# PIDDYBOT_V1.net
KiCad netlist of a schematic drawn in EAGLE
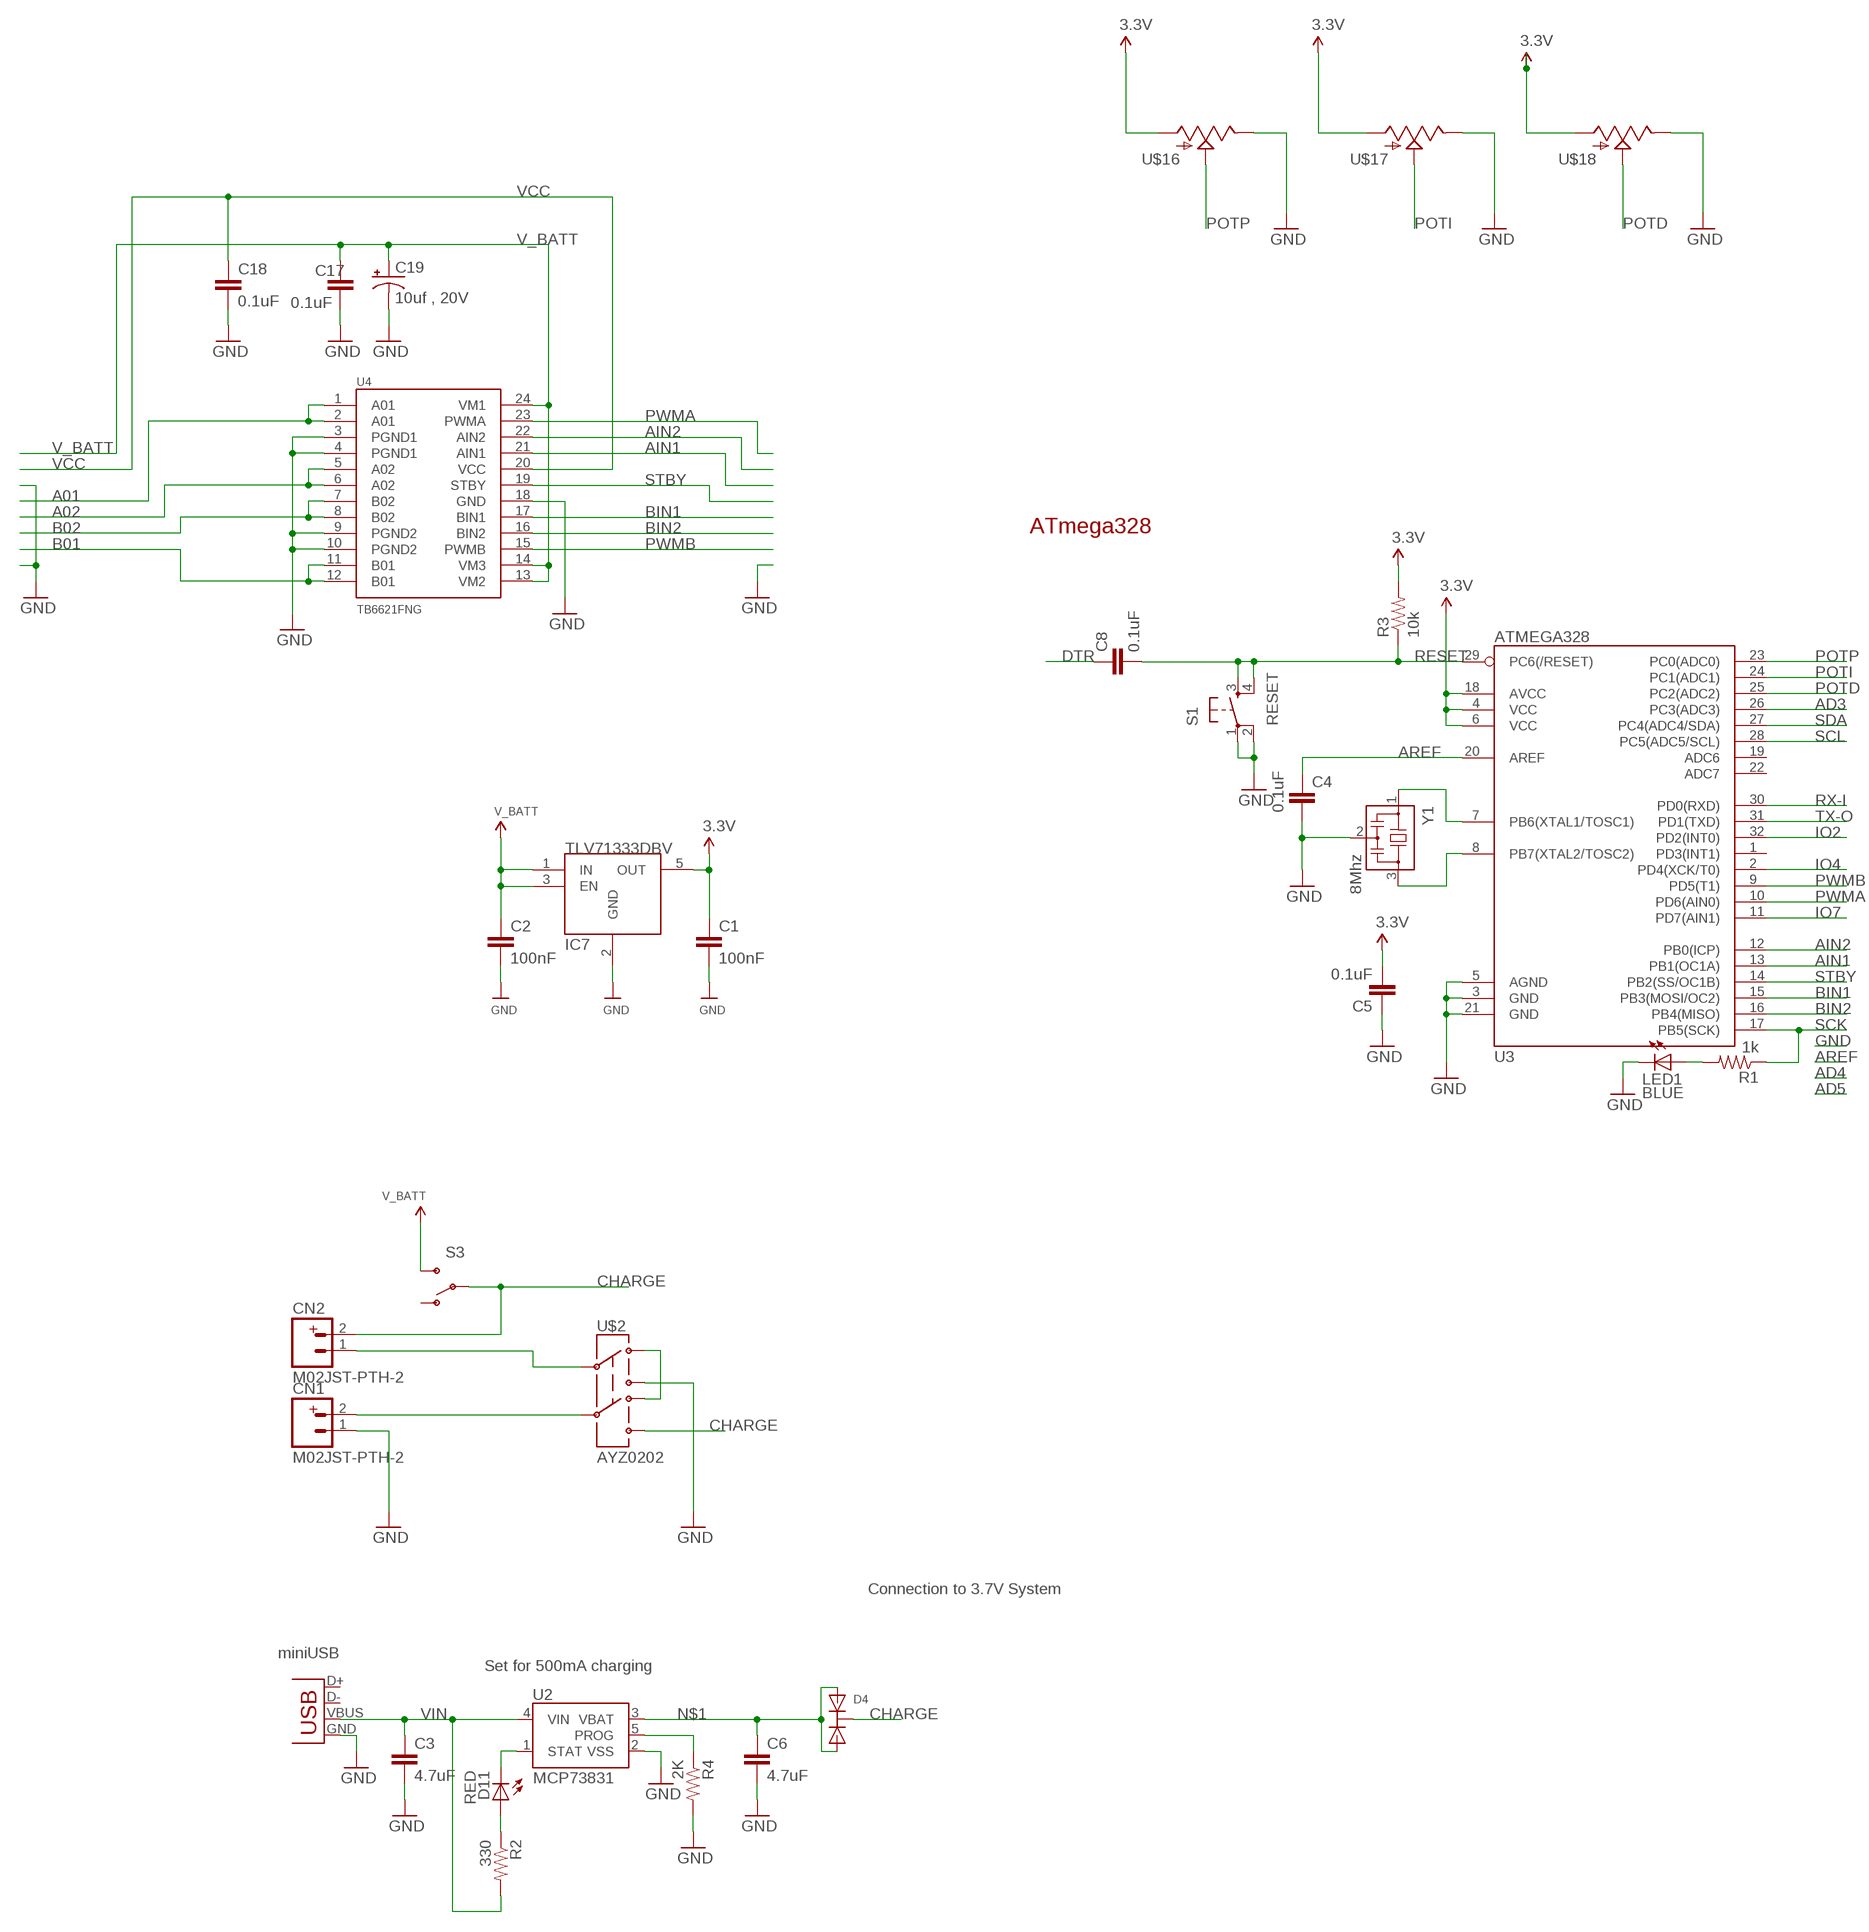
[diagram p0: schematic, sheet 1, part 1 of 2]
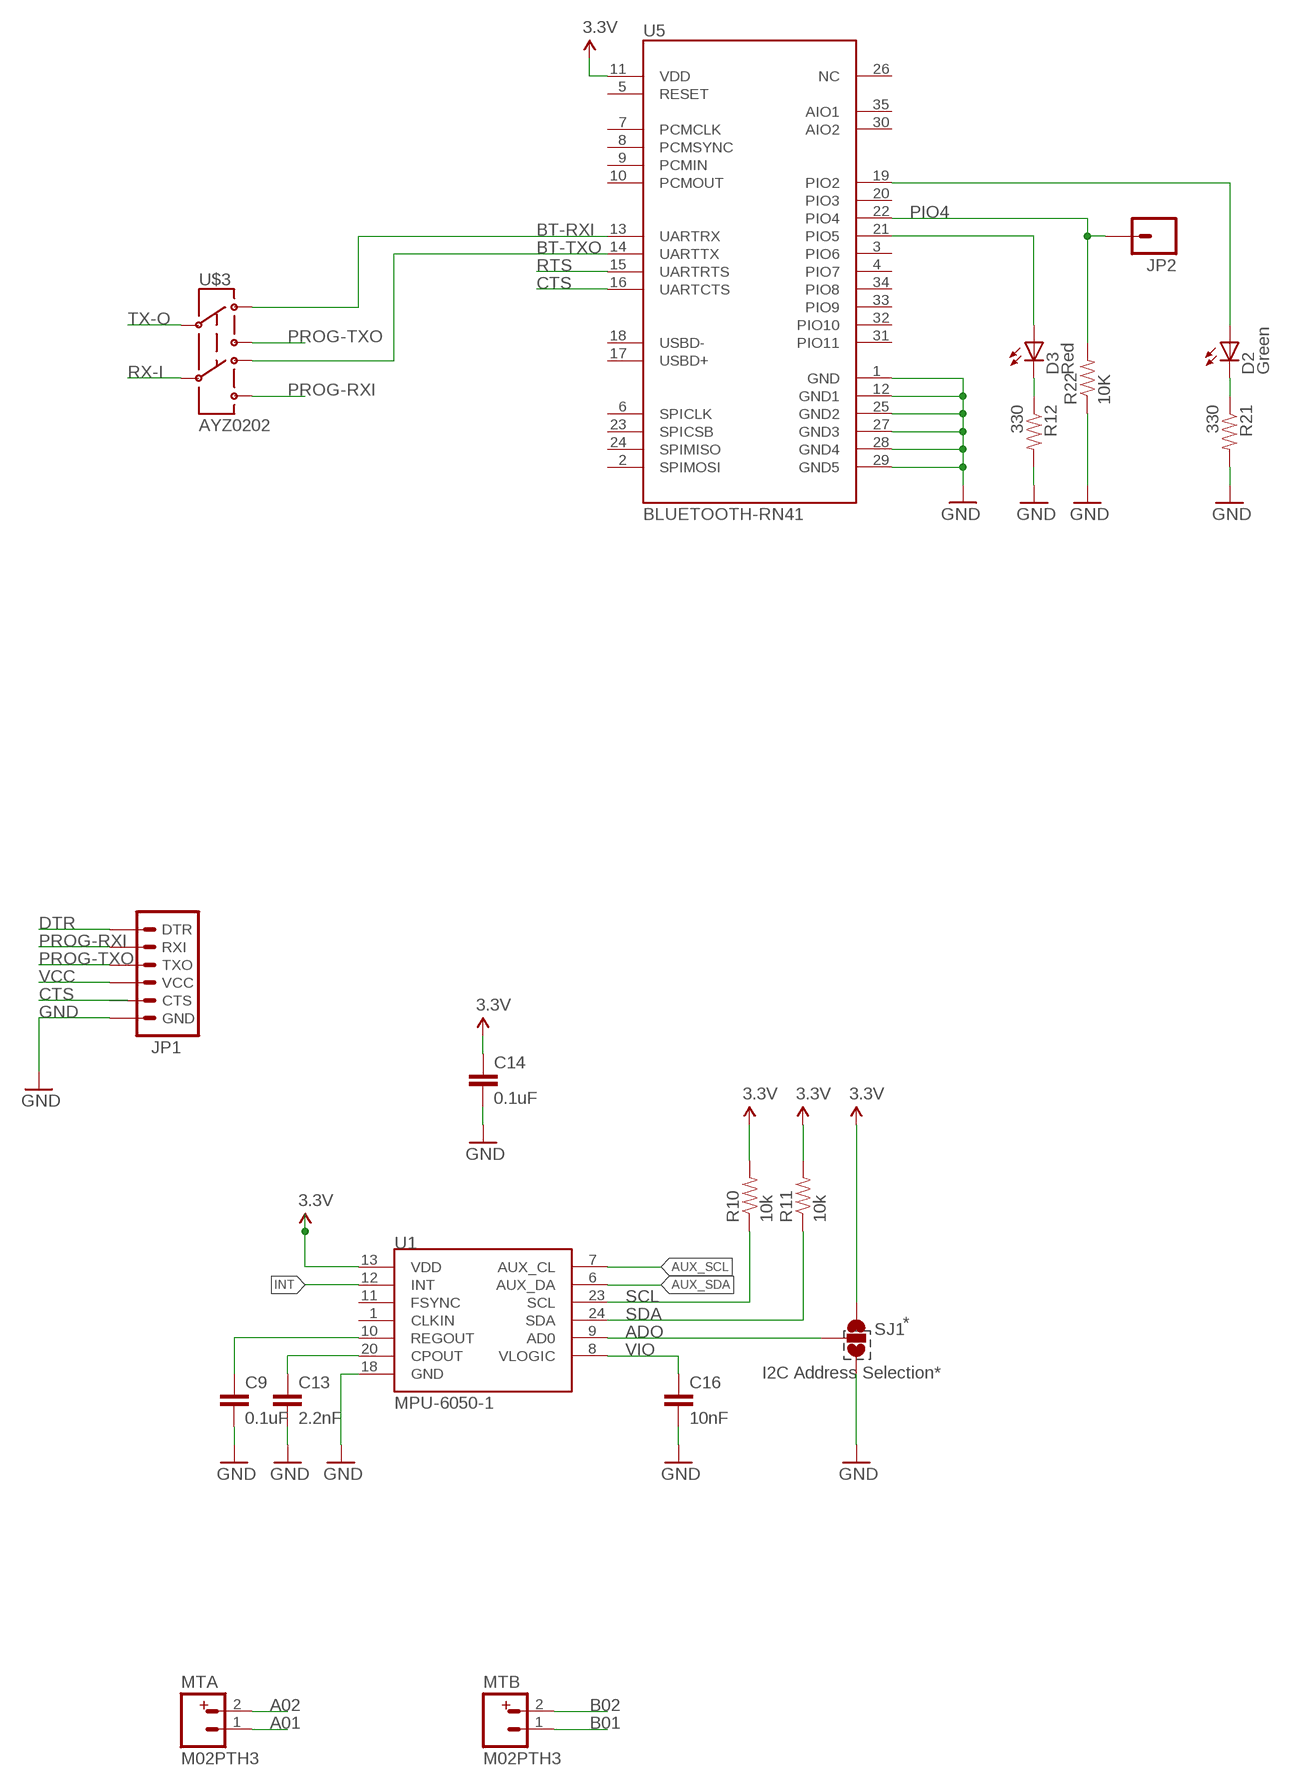
[diagram p1: schematic, sheet 1, part 2 of 2]

(export (version "E")
  (design (tool "Eeschema 10.0.6"))
  (components
    (comp (ref "C1")
      (value "100nF")
      (footprint "eagle-import:C0603K")
      (libsource (lib "eagle-import") (part "C-EUC0603K"))
    )
    (comp (ref "C2")
      (value "100nF")
      (footprint "eagle-import:C0603K")
      (libsource (lib "eagle-import") (part "C-EUC0603K"))
    )
    (comp (ref "C3")
      (value "4.7uF")
      (footprint "eagle-import:0402-CAP")
      (libsource (lib "eagle-import") (part "CAP0402-CAP"))
    )
    (comp (ref "C4")
      (value "0.1uF")
      (footprint "eagle-import:0402-CAP")
      (libsource (lib "eagle-import") (part "CAP0402-CAP"))
    )
    (comp (ref "C5")
      (value "0.1uF")
      (footprint "eagle-import:0402-CAP")
      (libsource (lib "eagle-import") (part "CAP0402-CAP"))
    )
    (comp (ref "C6")
      (value "4.7uF")
      (footprint "eagle-import:0402-CAP")
      (libsource (lib "eagle-import") (part "CAP0402-CAP"))
    )
    (comp (ref "C8")
      (value "0.1uF")
      (footprint "eagle-import:0402-CAP")
      (libsource (lib "eagle-import") (part "CAP0402-CAP"))
    )
    (comp (ref "C9")
      (value "0.1uF")
      (footprint "eagle-import:0603-CAP")
      (libsource (lib "eagle-import") (part "CAP0603-CAP"))
    )
    (comp (ref "C13")
      (value "2.2nF")
      (footprint "eagle-import:0603-CAP")
      (libsource (lib "eagle-import") (part "CAP0603-CAP"))
    )
    (comp (ref "C14")
      (value "0.1uF")
      (footprint "eagle-import:0603-CAP")
      (libsource (lib "eagle-import") (part "CAP0603-CAP"))
    )
    (comp (ref "C16")
      (value "10nF")
      (footprint "eagle-import:0603-CAP")
      (libsource (lib "eagle-import") (part "CAP0603-CAP"))
    )
    (comp (ref "C17")
      (value "0.1uF")
      (footprint "eagle-import:0402-CAP")
      (libsource (lib "eagle-import") (part "CAP0402-CAP"))
    )
    (comp (ref "C18")
      (value "0.1uF")
      (footprint "eagle-import:0402-CAP")
      (libsource (lib "eagle-import") (part "CAP0402-CAP"))
    )
    (comp (ref "C19")
      (value "10uf , 20V")
      (footprint "eagle-import:EIA3528")
      (libsource (lib "eagle-import") (part "CAP_POL3528"))
    )
    (comp (ref "CN1")
      (value "M02JST-PTH-2")
      (footprint "eagle-import:JST-2-PTH")
      (libsource (lib "eagle-import") (part "M02JST-PTH-2"))
    )
    (comp (ref "CN2")
      (value "M02JST-PTH-2")
      (footprint "eagle-import:JST-2-PTH")
      (libsource (lib "eagle-import") (part "M02JST-PTH-2"))
    )
    (comp (ref "D2")
      (value "Green")
      (footprint "eagle-import:LED-0603")
      (libsource (lib "eagle-import") (part "LED0603"))
    )
    (comp (ref "D3")
      (value "Red")
      (footprint "eagle-import:LED-0603")
      (libsource (lib "eagle-import") (part "LED0603"))
    )
    (comp (ref "D4")
      (value "BAT54C")
      (footprint "eagle-import:SOT23-R")
      (libsource (lib "eagle-import") (part "BAT54C"))
    )
    (comp (ref "D11")
      (value "RED")
      (footprint "eagle-import:LED-0603")
      (libsource (lib "eagle-import") (part "LED0603"))
    )
    (comp (ref "IC7")
      (value "TLV71333DBV")
      (footprint "eagle-import:SOT-23-5")
      (libsource (lib "eagle-import") (part "TLV713DBV33"))
    )
    (comp (ref "JP1")
      (value "ARDUINO_SERIAL_PROGRAMSMD")
      (footprint "eagle-import:1X06-SMD")
      (libsource (lib "eagle-import") (part "ARDUINO_SERIAL_PROGRAMSMD"))
    )
    (comp (ref "JP2")
      (value "M01SMDNS")
      (footprint "eagle-import:1X01NS")
      (libsource (lib "eagle-import") (part "M01SMDNS"))
    )
    (comp (ref "LED1")
      (value "BLUE")
      (footprint "eagle-import:LED-0603")
      (libsource (lib "eagle-import") (part "LED0603"))
    )
    (comp (ref "MTA")
      (value "M02PTH3")
      (footprint "eagle-import:1X02_LONGPADS")
      (libsource (lib "eagle-import") (part "M02PTH3"))
    )
    (comp (ref "MTB")
      (value "M02PTH3")
      (footprint "eagle-import:1X02_LONGPADS")
      (libsource (lib "eagle-import") (part "M02PTH3"))
    )
    (comp (ref "R1")
      (value "1k")
      (footprint "eagle-import:0402-RES")
      (libsource (lib "eagle-import") (part "RESISTOR0402-RES"))
    )
    (comp (ref "R2")
      (value "330")
      (footprint "eagle-import:0402-RES")
      (libsource (lib "eagle-import") (part "RESISTOR0402-RES"))
    )
    (comp (ref "R3")
      (value "10k")
      (footprint "eagle-import:0402-RES")
      (libsource (lib "eagle-import") (part "RESISTOR0402-RES"))
    )
    (comp (ref "R4")
      (value "2K")
      (footprint "eagle-import:0402-RES")
      (libsource (lib "eagle-import") (part "RESISTOR0402-RES"))
    )
    (comp (ref "R10")
      (value "10k")
      (footprint "eagle-import:0603-RES")
      (libsource (lib "eagle-import") (part "RESISTOR0603-RES"))
    )
    (comp (ref "R11")
      (value "10k")
      (footprint "eagle-import:0603-RES")
      (libsource (lib "eagle-import") (part "RESISTOR0603-RES"))
    )
    (comp (ref "R12")
      (value "330")
      (footprint "eagle-import:0402-RES")
      (libsource (lib "eagle-import") (part "RESISTOR0402-RES"))
    )
    (comp (ref "R21")
      (value "330")
      (footprint "eagle-import:0402-RES")
      (libsource (lib "eagle-import") (part "RESISTOR0402-RES"))
    )
    (comp (ref "R22")
      (value "10K")
      (footprint "eagle-import:0402-RES")
      (libsource (lib "eagle-import") (part "RESISTOR0402-RES"))
    )
    (comp (ref "S1")
      (value "RESET")
      (footprint "eagle-import:TACTILE_SWITCH_SMD")
      (libsource (lib "eagle-import") (part "TAC_SWITCHSMD"))
    )
    (comp (ref "S3")
      (value "SWITCH-SPDTPTH")
      (footprint "eagle-import:SWITCH-SPDT")
      (libsource (lib "eagle-import") (part "SWITCH-SPDTPTH"))
    )
    (comp (ref "SJ1")
      (value "SOLDERJUMPER_2WAYPASTE2&3")
      (footprint "eagle-import:SJ_3_PASTE2&3")
      (libsource (lib "eagle-import") (part "SOLDERJUMPER_2WAYPASTE2&3"))
    )
    (comp (ref "U$2")
      (value "AYZ0202")
      (footprint "eagle-import:AYZ0202")
      (libsource (lib "eagle-import") (part "AYZ0202"))
    )
    (comp (ref "U$3")
      (value "AYZ0202")
      (footprint "eagle-import:AYZ0202")
      (libsource (lib "eagle-import") (part "AYZ0202"))
    )
    (comp (ref "U$16")
      (value "POT")
      (footprint "eagle-import:ALPS_POT")
      (libsource (lib "eagle-import") (part "POT"))
    )
    (comp (ref "U$17")
      (value "POT")
      (footprint "eagle-import:ALPS_POT")
      (libsource (lib "eagle-import") (part "POT"))
    )
    (comp (ref "U$18")
      (value "POT")
      (footprint "eagle-import:ALPS_POT")
      (libsource (lib "eagle-import") (part "POT"))
    )
    (comp (ref "U1")
      (value "MPU-6050-1")
      (footprint "eagle-import:QFN-24-4MM2")
      (libsource (lib "eagle-import") (part "MPU-6050-1"))
    )
    (comp (ref "U2")
      (value "MCP73831")
      (footprint "eagle-import:SOT23-5")
      (libsource (lib "eagle-import") (part "MCP73831"))
    )
    (comp (ref "U3")
      (value "ATMEGA328")
      (footprint "eagle-import:TQFP32-08")
      (libsource (lib "eagle-import") (part "ATMEGA168"))
    )
    (comp (ref "U4")
      (value "TB6621FNG")
      (footprint "eagle-import:SSOP24")
      (libsource (lib "eagle-import") (part "TB6621FNG"))
    )
    (comp (ref "U5")
      (value "BLUETOOTH-RN41")
      (footprint "eagle-import:RN41")
      (libsource (lib "eagle-import") (part "BLUETOOTH-RN41{dblquote}"))
    )
    (comp (ref "X1")
      (value "Micro USB")
      (footprint "eagle-import:USB-MINIB")
      (libsource (lib "eagle-import") (part "USBSMD"))
    )
    (comp (ref "Y1")
      (value "8Mhz")
      (footprint "eagle-import:CSTCR6M")
      (fields (field (name "MPN") "CSTCR6M00G53-R0"))
      (libsource (lib "eagle-import") (part "CSTCR6M00G53Z"))
    )
  )
  (nets
    (net (code "1") (name "/A01") (class "Default")
      (node (ref "MTA") (pin "1") (pinfunction "1_1") (pintype "passive"))
      (node (ref "U4") (pin "1") (pinfunction "A01_1") (pintype "bidirectional"))
      (node (ref "U4") (pin "2") (pinfunction "A01_2") (pintype "bidirectional"))
    )
    (net (code "2") (name "/A02") (class "Default")
      (node (ref "MTA") (pin "2") (pinfunction "2_2") (pintype "passive"))
      (node (ref "U4") (pin "5") (pinfunction "A02_5") (pintype "bidirectional"))
      (node (ref "U4") (pin "6") (pinfunction "A02_6") (pintype "bidirectional"))
    )
    (net (code "3") (name "/AD3") (class "Default")
      (node (ref "U3") (pin "26") (pinfunction "PC3(ADC3)_26") (pintype "bidirectional"))
    )
    (net (code "6") (name "/ADO") (class "Default")
      (node (ref "SJ1") (pin "2") (pinfunction "2_2") (pintype "passive"))
      (node (ref "U1") (pin "9") (pinfunction "AD0_9") (pintype "bidirectional"))
    )
    (net (code "7") (name "/AIN1") (class "Default")
      (node (ref "U3") (pin "13") (pinfunction "PB1(OC1A)_13") (pintype "bidirectional"))
      (node (ref "U4") (pin "21") (pinfunction "AIN1_21") (pintype "bidirectional"))
    )
    (net (code "8") (name "/AIN2") (class "Default")
      (node (ref "U3") (pin "12") (pinfunction "PB0(ICP)_12") (pintype "bidirectional"))
      (node (ref "U4") (pin "22") (pinfunction "AIN2_22") (pintype "bidirectional"))
    )
    (net (code "9") (name "/AREF") (class "Default")
      (node (ref "C4") (pin "1") (pinfunction "1_1") (pintype "passive"))
      (node (ref "U3") (pin "20") (pinfunction "AREF_20") (pintype "bidirectional"))
    )
    (net (code "10") (name "/B01") (class "Default")
      (node (ref "MTB") (pin "1") (pinfunction "1_1") (pintype "passive"))
      (node (ref "U4") (pin "11") (pinfunction "B01_11") (pintype "bidirectional"))
      (node (ref "U4") (pin "12") (pinfunction "B01_12") (pintype "bidirectional"))
    )
    (net (code "11") (name "/B02") (class "Default")
      (node (ref "MTB") (pin "2") (pinfunction "2_2") (pintype "passive"))
      (node (ref "U4") (pin "7") (pinfunction "B02_7") (pintype "bidirectional"))
      (node (ref "U4") (pin "8") (pinfunction "B02_8") (pintype "bidirectional"))
    )
    (net (code "12") (name "/BIN1") (class "Default")
      (node (ref "U3") (pin "15") (pinfunction "PB3(MOSI/OC2)_15") (pintype "bidirectional"))
      (node (ref "U4") (pin "17") (pinfunction "BIN1_17") (pintype "bidirectional"))
    )
    (net (code "13") (name "/BIN2") (class "Default")
      (node (ref "U3") (pin "16") (pinfunction "PB4(MISO)_16") (pintype "bidirectional"))
      (node (ref "U4") (pin "16") (pinfunction "BIN2_16") (pintype "bidirectional"))
    )
    (net (code "14") (name "/BT-RXI") (class "Default")
      (node (ref "U$3") (pin "3") (pinfunction "1_3") (pintype "bidirectional"))
      (node (ref "U5") (pin "13") (pinfunction "UARTRX_13") (pintype "bidirectional"))
    )
    (net (code "15") (name "/BT-TXO") (class "Default")
      (node (ref "U$3") (pin "6") (pinfunction "4_6") (pintype "bidirectional"))
      (node (ref "U5") (pin "14") (pinfunction "UARTTX_14") (pintype "bidirectional"))
    )
    (net (code "16") (name "/CHARGE") (class "Default")
      (node (ref "CN2") (pin "2") (pinfunction "2_2") (pintype "passive"))
      (node (ref "D4") (pin "3") (pinfunction "C_3") (pintype "passive"))
      (node (ref "S3") (pin "2") (pinfunction "P_2") (pintype "passive"))
      (node (ref "U$2") (pin "4") (pinfunction "6_4") (pintype "bidirectional"))
    )
    (net (code "17") (name "/CTS") (class "Default")
      (node (ref "U5") (pin "16") (pinfunction "UARTCTS_16") (pintype "bidirectional"))
    )
    (net (code "18") (name "/DTR") (class "Default")
      (node (ref "C8") (pin "1") (pinfunction "1_1") (pintype "passive"))
      (node (ref "JP1") (pin "1") (pinfunction "DTR_1") (pintype "passive"))
    )
    (net (code "19") (name "/IO2") (class "Default")
      (node (ref "U3") (pin "32") (pinfunction "PD2(INT0)_32") (pintype "bidirectional"))
    )
    (net (code "20") (name "/IO4") (class "Default")
      (node (ref "U3") (pin "2") (pinfunction "PD4(XCK/T0)_2") (pintype "bidirectional"))
    )
    (net (code "21") (name "/IO7") (class "Default")
      (node (ref "U3") (pin "11") (pinfunction "PD7(AIN1)_11") (pintype "bidirectional"))
    )
    (net (code "22") (name "/N$1") (class "Default")
      (node (ref "C6") (pin "1") (pinfunction "1_1") (pintype "passive"))
      (node (ref "D4") (pin "1") (pinfunction "A1_1") (pintype "passive"))
      (node (ref "D4") (pin "2") (pinfunction "A2_2") (pintype "passive"))
      (node (ref "U2") (pin "3") (pinfunction "VBAT_3") (pintype "power_in"))
    )
    (net (code "23") (name "/PIO4") (class "Default")
      (node (ref "JP2") (pin "1") (pinfunction "1_1") (pintype "passive"))
      (node (ref "R22") (pin "2") (pinfunction "2_2") (pintype "passive"))
      (node (ref "U5") (pin "22") (pinfunction "PIO4_22") (pintype "bidirectional"))
    )
    (net (code "24") (name "/POTD") (class "Default")
      (node (ref "U$18") (pin "P$2") (pinfunction "S_P$2") (pintype "passive"))
      (node (ref "U3") (pin "25") (pinfunction "PC2(ADC2)_25") (pintype "bidirectional"))
    )
    (net (code "25") (name "/POTI") (class "Default")
      (node (ref "U$17") (pin "P$2") (pinfunction "S_P$2") (pintype "passive"))
      (node (ref "U3") (pin "24") (pinfunction "PC1(ADC1)_24") (pintype "bidirectional"))
    )
    (net (code "26") (name "/POTP") (class "Default")
      (node (ref "U$16") (pin "P$2") (pinfunction "S_P$2") (pintype "passive"))
      (node (ref "U3") (pin "23") (pinfunction "PC0(ADC0)_23") (pintype "bidirectional"))
    )
    (net (code "27") (name "/PROG-RXI") (class "Default")
      (node (ref "JP1") (pin "2") (pinfunction "RXI_2") (pintype "passive"))
      (node (ref "U$3") (pin "4") (pinfunction "6_4") (pintype "bidirectional"))
    )
    (net (code "28") (name "/PROG-TXO") (class "Default")
      (node (ref "JP1") (pin "3") (pinfunction "TXO_3") (pintype "passive"))
      (node (ref "U$3") (pin "1") (pinfunction "3_1") (pintype "bidirectional"))
    )
    (net (code "29") (name "/PWMA") (class "Default")
      (node (ref "U3") (pin "10") (pinfunction "PD6(AIN0)_10") (pintype "bidirectional"))
      (node (ref "U4") (pin "23") (pinfunction "PWMA_23") (pintype "bidirectional"))
    )
    (net (code "30") (name "/PWMB") (class "Default")
      (node (ref "U3") (pin "9") (pinfunction "PD5(T1)_9") (pintype "bidirectional"))
      (node (ref "U4") (pin "15") (pinfunction "PWMB_15") (pintype "bidirectional"))
    )
    (net (code "31") (name "/RESET") (class "Default")
      (node (ref "C8") (pin "2") (pinfunction "2_2") (pintype "passive"))
      (node (ref "R3") (pin "1") (pinfunction "1_1") (pintype "passive"))
      (node (ref "S1") (pin "3") (pinfunction "3_3") (pintype "passive"))
      (node (ref "S1") (pin "4") (pinfunction "4_4") (pintype "passive"))
      (node (ref "U3") (pin "29") (pinfunction "PC6(/RESET)_29") (pintype "bidirectional"))
    )
    (net (code "32") (name "/RTS") (class "Default")
      (node (ref "U5") (pin "15") (pinfunction "UARTRTS_15") (pintype "bidirectional"))
    )
    (net (code "33") (name "/RX-I") (class "Default")
      (node (ref "U$3") (pin "5") (pinfunction "5_5") (pintype "bidirectional"))
      (node (ref "U3") (pin "30") (pinfunction "PD0(RXD)_30") (pintype "bidirectional"))
    )
    (net (code "34") (name "/SCK") (class "Default")
      (node (ref "R1") (pin "1") (pinfunction "1_1") (pintype "passive"))
      (node (ref "U3") (pin "17") (pinfunction "PB5(SCK)_17") (pintype "bidirectional"))
    )
    (net (code "35") (name "/SCL") (class "Default")
      (node (ref "R10") (pin "1") (pinfunction "1_1") (pintype "passive"))
      (node (ref "U1") (pin "23") (pinfunction "SCL_23") (pintype "bidirectional"))
      (node (ref "U3") (pin "28") (pinfunction "PC5(ADC5/SCL)_28") (pintype "bidirectional"))
    )
    (net (code "36") (name "/SDA") (class "Default")
      (node (ref "R11") (pin "1") (pinfunction "1_1") (pintype "passive"))
      (node (ref "U1") (pin "24") (pinfunction "SDA_24") (pintype "bidirectional"))
      (node (ref "U3") (pin "27") (pinfunction "PC4(ADC4/SDA)_27") (pintype "bidirectional"))
    )
    (net (code "37") (name "/STBY") (class "Default")
      (node (ref "U3") (pin "14") (pinfunction "PB2(SS/OC1B)_14") (pintype "bidirectional"))
      (node (ref "U4") (pin "19") (pinfunction "STBY_19") (pintype "bidirectional"))
    )
    (net (code "38") (name "/TX-O") (class "Default")
      (node (ref "U$3") (pin "2") (pinfunction "2_2") (pintype "bidirectional"))
      (node (ref "U3") (pin "31") (pinfunction "PD1(TXD)_31") (pintype "bidirectional"))
    )
    (net (code "39") (name "/VIN") (class "Default")
      (node (ref "C3") (pin "1") (pinfunction "1_1") (pintype "passive"))
      (node (ref "R2") (pin "2") (pinfunction "2_2") (pintype "passive"))
      (node (ref "U2") (pin "4") (pinfunction "VIN_4") (pintype "power_in"))
      (node (ref "X1") (pin "VBUS") (pinfunction "VBUS_VBUS") (pintype "bidirectional"))
    )
    (net (code "40") (name "/VIO") (class "Default")
      (node (ref "C16") (pin "1") (pinfunction "1_1") (pintype "passive"))
      (node (ref "U1") (pin "8") (pinfunction "VLOGIC_8") (pintype "bidirectional"))
    )
    (net (code "41") (name "3.3V") (class "Default")
      (node (ref "C1") (pin "1") (pinfunction "1_1") (pintype "passive"))
      (node (ref "C14") (pin "1") (pinfunction "1_1") (pintype "passive"))
      (node (ref "C18") (pin "1") (pinfunction "1_1") (pintype "passive"))
      (node (ref "C5") (pin "2") (pinfunction "2_2") (pintype "passive"))
      (node (ref "IC7") (pin "5") (pinfunction "OUT_5") (pintype "power_in"))
      (node (ref "JP1") (pin "4") (pinfunction "VCC_4") (pintype "passive"))
      (node (ref "R10") (pin "2") (pinfunction "2_2") (pintype "passive"))
      (node (ref "R11") (pin "2") (pinfunction "2_2") (pintype "passive"))
      (node (ref "R3") (pin "2") (pinfunction "2_2") (pintype "passive"))
      (node (ref "SJ1") (pin "1") (pinfunction "1_1") (pintype "passive"))
      (node (ref "U$16") (pin "P$3") (pinfunction "A_P$3") (pintype "passive"))
      (node (ref "U$17") (pin "P$3") (pinfunction "A_P$3") (pintype "passive"))
      (node (ref "U$18") (pin "P$3") (pinfunction "A_P$3") (pintype "passive"))
      (node (ref "U1") (pin "13") (pinfunction "VDD_13") (pintype "bidirectional"))
      (node (ref "U3") (pin "18") (pinfunction "AVCC_18") (pintype "bidirectional"))
      (node (ref "U3") (pin "4") (pinfunction "VCC_4") (pintype "bidirectional"))
      (node (ref "U3") (pin "6") (pinfunction "VCC_6") (pintype "bidirectional"))
      (node (ref "U4") (pin "20") (pinfunction "VCC_20") (pintype "bidirectional"))
      (node (ref "U5") (pin "11") (pinfunction "VDD_11") (pintype "bidirectional"))
    )
    (net (code "42") (name "AUX_SCL") (class "Default")
      (node (ref "U1") (pin "7") (pinfunction "AUX_CL_7") (pintype "bidirectional"))
    )
    (net (code "43") (name "AUX_SDA") (class "Default")
      (node (ref "U1") (pin "6") (pinfunction "AUX_DA_6") (pintype "bidirectional"))
    )
    (net (code "44") (name "GND") (class "Default")
      (node (ref "C1") (pin "2") (pinfunction "2_2") (pintype "passive"))
      (node (ref "C13") (pin "2") (pinfunction "2_2") (pintype "passive"))
      (node (ref "C14") (pin "2") (pinfunction "2_2") (pintype "passive"))
      (node (ref "C16") (pin "2") (pinfunction "2_2") (pintype "passive"))
      (node (ref "C17") (pin "2") (pinfunction "2_2") (pintype "passive"))
      (node (ref "C18") (pin "2") (pinfunction "2_2") (pintype "passive"))
      (node (ref "C19") (pin "C") (pinfunction "-_C") (pintype "passive"))
      (node (ref "C2") (pin "2") (pinfunction "2_2") (pintype "passive"))
      (node (ref "C3") (pin "2") (pinfunction "2_2") (pintype "passive"))
      (node (ref "C4") (pin "2") (pinfunction "2_2") (pintype "passive"))
      (node (ref "C5") (pin "1") (pinfunction "1_1") (pintype "passive"))
      (node (ref "C6") (pin "2") (pinfunction "2_2") (pintype "passive"))
      (node (ref "C9") (pin "2") (pinfunction "2_2") (pintype "passive"))
      (node (ref "CN1") (pin "1") (pinfunction "1_1") (pintype "passive"))
      (node (ref "IC7") (pin "2") (pinfunction "GND_2") (pintype "power_in"))
      (node (ref "JP1") (pin "6") (pinfunction "GND_6") (pintype "passive"))
      (node (ref "LED1") (pin "C") (pinfunction "C_C") (pintype "passive"))
      (node (ref "R12") (pin "2") (pinfunction "2_2") (pintype "passive"))
      (node (ref "R21") (pin "2") (pinfunction "2_2") (pintype "passive"))
      (node (ref "R22") (pin "1") (pinfunction "1_1") (pintype "passive"))
      (node (ref "R4") (pin "2") (pinfunction "2_2") (pintype "passive"))
      (node (ref "S1") (pin "1") (pinfunction "1_1") (pintype "passive"))
      (node (ref "S1") (pin "2") (pinfunction "2_2") (pintype "passive"))
      (node (ref "SJ1") (pin "3") (pinfunction "3_3") (pintype "passive"))
      (node (ref "U$16") (pin "P$1") (pinfunction "E_P$1") (pintype "passive"))
      (node (ref "U$17") (pin "P$1") (pinfunction "E_P$1") (pintype "passive"))
      (node (ref "U$18") (pin "P$1") (pinfunction "E_P$1") (pintype "passive"))
      (node (ref "U$2") (pin "1") (pinfunction "3_1") (pintype "bidirectional"))
      (node (ref "U1") (pin "18") (pinfunction "GND_18") (pintype "bidirectional"))
      (node (ref "U2") (pin "2") (pinfunction "VSS_2") (pintype "power_in"))
      (node (ref "U3") (pin "21") (pinfunction "GND_21") (pintype "bidirectional"))
      (node (ref "U3") (pin "3") (pinfunction "GND_3") (pintype "bidirectional"))
      (node (ref "U3") (pin "5") (pinfunction "AGND_5") (pintype "bidirectional"))
      (node (ref "U4") (pin "10") (pinfunction "PGND2_10") (pintype "bidirectional"))
      (node (ref "U4") (pin "18") (pinfunction "GND_18") (pintype "bidirectional"))
      (node (ref "U4") (pin "3") (pinfunction "PGND1_3") (pintype "bidirectional"))
      (node (ref "U4") (pin "4") (pinfunction "PGND1_4") (pintype "bidirectional"))
      (node (ref "U4") (pin "9") (pinfunction "PGND2_9") (pintype "bidirectional"))
      (node (ref "U5") (pin "1") (pinfunction "GND_1") (pintype "bidirectional"))
      (node (ref "U5") (pin "12") (pinfunction "GND1_12") (pintype "bidirectional"))
      (node (ref "U5") (pin "25") (pinfunction "GND2_25") (pintype "bidirectional"))
      (node (ref "U5") (pin "27") (pinfunction "GND3_27") (pintype "bidirectional"))
      (node (ref "U5") (pin "28") (pinfunction "GND4_28") (pintype "bidirectional"))
      (node (ref "U5") (pin "29") (pinfunction "GND5_29") (pintype "bidirectional"))
      (node (ref "X1") (pin "GND") (pinfunction "GND_GND") (pintype "bidirectional"))
      (node (ref "Y1") (pin "2") (pinfunction "2_2") (pintype "passive"))
    )
    (net (code "45") (name "INT") (class "Default")
      (node (ref "U1") (pin "12") (pinfunction "INT_12") (pintype "bidirectional"))
    )
    (net (code "46") (name "Net-(CN1-Pad2)") (class "Default")
      (node (ref "CN1") (pin "2") (pinfunction "2_2") (pintype "passive"))
      (node (ref "U$2") (pin "5") (pinfunction "5_5") (pintype "bidirectional"))
    )
    (net (code "47") (name "Net-(CN2-Pad1)") (class "Default")
      (node (ref "CN2") (pin "1") (pinfunction "1_1") (pintype "passive"))
      (node (ref "U$2") (pin "2") (pinfunction "2_2") (pintype "bidirectional"))
    )
    (net (code "48") (name "Net-(D2-PadC)") (class "Default")
      (node (ref "D2") (pin "C") (pinfunction "C_C") (pintype "passive"))
      (node (ref "R21") (pin "1") (pinfunction "1_1") (pintype "passive"))
    )
    (net (code "49") (name "Net-(D3-PadC)") (class "Default")
      (node (ref "D3") (pin "C") (pinfunction "C_C") (pintype "passive"))
      (node (ref "R12") (pin "1") (pinfunction "1_1") (pintype "passive"))
    )
    (net (code "50") (name "Net-(D11-PadA)") (class "Default")
      (node (ref "D11") (pin "A") (pinfunction "A_A") (pintype "passive"))
      (node (ref "R2") (pin "1") (pinfunction "1_1") (pintype "passive"))
    )
    (net (code "51") (name "Net-(LED1-PadA)") (class "Default")
      (node (ref "LED1") (pin "A") (pinfunction "A_A") (pintype "passive"))
      (node (ref "R1") (pin "2") (pinfunction "2_2") (pintype "passive"))
    )
    (net (code "52") (name "Net-(U$2-1)") (class "Default")
      (node (ref "U$2") (pin "3") (pinfunction "1_3") (pintype "bidirectional"))
      (node (ref "U$2") (pin "6") (pinfunction "4_6") (pintype "bidirectional"))
    )
    (net (code "53") (name "Net-(U1-CPOUT)") (class "Default")
      (node (ref "C13") (pin "1") (pinfunction "1_1") (pintype "passive"))
      (node (ref "U1") (pin "20") (pinfunction "CPOUT_20") (pintype "bidirectional"))
    )
    (net (code "54") (name "Net-(U1-REGOUT)") (class "Default")
      (node (ref "C9") (pin "1") (pinfunction "1_1") (pintype "passive"))
      (node (ref "U1") (pin "10") (pinfunction "REGOUT_10") (pintype "bidirectional"))
    )
    (net (code "55") (name "Net-(U2-PROG)") (class "Default")
      (node (ref "R4") (pin "1") (pinfunction "1_1") (pintype "passive"))
      (node (ref "U2") (pin "5") (pinfunction "PROG_5") (pintype "input"))
    )
    (net (code "56") (name "Net-(U2-STAT)") (class "Default")
      (node (ref "D11") (pin "C") (pinfunction "C_C") (pintype "passive"))
      (node (ref "U2") (pin "1") (pinfunction "STAT_1") (pintype "output"))
    )
    (net (code "57") (name "Net-(U3-PB6(XTAL1{slash}TOSC1))") (class "Default")
      (node (ref "U3") (pin "7") (pinfunction "PB6(XTAL1/TOSC1)_7") (pintype "bidirectional"))
      (node (ref "Y1") (pin "1") (pinfunction "1_1") (pintype "passive"))
    )
    (net (code "58") (name "Net-(U3-PB7(XTAL2{slash}TOSC2))") (class "Default")
      (node (ref "U3") (pin "8") (pinfunction "PB7(XTAL2/TOSC2)_8") (pintype "bidirectional"))
      (node (ref "Y1") (pin "3") (pinfunction "3_3") (pintype "passive"))
    )
    (net (code "59") (name "Net-(U5-PIO2)") (class "Default")
      (node (ref "D2") (pin "A") (pinfunction "A_A") (pintype "passive"))
      (node (ref "U5") (pin "19") (pinfunction "PIO2_19") (pintype "bidirectional"))
    )
    (net (code "60") (name "Net-(U5-PIO5)") (class "Default")
      (node (ref "D3") (pin "A") (pinfunction "A_A") (pintype "passive"))
      (node (ref "U5") (pin "21") (pinfunction "PIO5_21") (pintype "bidirectional"))
    )
    (net (code "61") (name "V_BATT") (class "Default")
      (node (ref "C17") (pin "1") (pinfunction "1_1") (pintype "passive"))
      (node (ref "C19") (pin "A") (pinfunction "+_A") (pintype "passive"))
      (node (ref "C2") (pin "1") (pinfunction "1_1") (pintype "passive"))
      (node (ref "IC7") (pin "1") (pinfunction "IN_1") (pintype "power_in"))
      (node (ref "IC7") (pin "3") (pinfunction "EN_3") (pintype "input"))
      (node (ref "S3") (pin "3") (pinfunction "S_3") (pintype "passive"))
      (node (ref "U4") (pin "13") (pinfunction "VM2_13") (pintype "bidirectional"))
      (node (ref "U4") (pin "14") (pinfunction "VM3_14") (pintype "bidirectional"))
      (node (ref "U4") (pin "24") (pinfunction "VM1_24") (pintype "bidirectional"))
    )
    (net (code "62") (name "unconnected-(JP1-CTS-Pad5)") (class "Default")
      (node (ref "JP1") (pin "5") (pinfunction "CTS_5") (pintype "passive"))
    )
    (net (code "63") (name "unconnected-(S3-O-Pad1)") (class "Default")
      (node (ref "S3") (pin "1") (pinfunction "O_1") (pintype "passive"))
    )
    (net (code "64") (name "unconnected-(U1-CLKIN-Pad1)") (class "Default")
      (node (ref "U1") (pin "1") (pinfunction "CLKIN_1") (pintype "bidirectional"))
    )
    (net (code "65") (name "unconnected-(U1-FSYNC-Pad11)") (class "Default")
      (node (ref "U1") (pin "11") (pinfunction "FSYNC_11") (pintype "bidirectional"))
    )
    (net (code "66") (name "unconnected-(U3-ADC6-Pad19)") (class "Default")
      (node (ref "U3") (pin "19") (pinfunction "ADC6_19") (pintype "bidirectional"))
    )
    (net (code "67") (name "unconnected-(U3-ADC7-Pad22)") (class "Default")
      (node (ref "U3") (pin "22") (pinfunction "ADC7_22") (pintype "bidirectional"))
    )
    (net (code "68") (name "unconnected-(U3-PD3(INT1)-Pad1)") (class "Default")
      (node (ref "U3") (pin "1") (pinfunction "PD3(INT1)_1") (pintype "bidirectional"))
    )
    (net (code "69") (name "unconnected-(U5-AIO1-Pad35)") (class "Default")
      (node (ref "U5") (pin "35") (pinfunction "AIO1_35") (pintype "bidirectional"))
    )
    (net (code "70") (name "unconnected-(U5-AIO2-Pad30)") (class "Default")
      (node (ref "U5") (pin "30") (pinfunction "AIO2_30") (pintype "bidirectional"))
    )
    (net (code "71") (name "unconnected-(U5-NC-Pad26)") (class "Default")
      (node (ref "U5") (pin "26") (pinfunction "NC_26") (pintype "bidirectional"))
    )
    (net (code "72") (name "unconnected-(U5-PCMCLK-Pad7)") (class "Default")
      (node (ref "U5") (pin "7") (pinfunction "PCMCLK_7") (pintype "bidirectional"))
    )
    (net (code "73") (name "unconnected-(U5-PCMIN-Pad9)") (class "Default")
      (node (ref "U5") (pin "9") (pinfunction "PCMIN_9") (pintype "bidirectional"))
    )
    (net (code "74") (name "unconnected-(U5-PCMOUT-Pad10)") (class "Default")
      (node (ref "U5") (pin "10") (pinfunction "PCMOUT_10") (pintype "bidirectional"))
    )
    (net (code "75") (name "unconnected-(U5-PCMSYNC-Pad8)") (class "Default")
      (node (ref "U5") (pin "8") (pinfunction "PCMSYNC_8") (pintype "bidirectional"))
    )
    (net (code "76") (name "unconnected-(U5-PIO3-Pad20)") (class "Default")
      (node (ref "U5") (pin "20") (pinfunction "PIO3_20") (pintype "bidirectional"))
    )
    (net (code "77") (name "unconnected-(U5-PIO6-Pad3)") (class "Default")
      (node (ref "U5") (pin "3") (pinfunction "PIO6_3") (pintype "bidirectional"))
    )
    (net (code "78") (name "unconnected-(U5-PIO7-Pad4)") (class "Default")
      (node (ref "U5") (pin "4") (pinfunction "PIO7_4") (pintype "bidirectional"))
    )
    (net (code "79") (name "unconnected-(U5-PIO8-Pad34)") (class "Default")
      (node (ref "U5") (pin "34") (pinfunction "PIO8_34") (pintype "bidirectional"))
    )
    (net (code "80") (name "unconnected-(U5-PIO9-Pad33)") (class "Default")
      (node (ref "U5") (pin "33") (pinfunction "PIO9_33") (pintype "bidirectional"))
    )
    (net (code "81") (name "unconnected-(U5-PIO10-Pad32)") (class "Default")
      (node (ref "U5") (pin "32") (pinfunction "PIO10_32") (pintype "bidirectional"))
    )
    (net (code "82") (name "unconnected-(U5-PIO11-Pad31)") (class "Default")
      (node (ref "U5") (pin "31") (pinfunction "PIO11_31") (pintype "bidirectional"))
    )
    (net (code "83") (name "unconnected-(U5-RESET-Pad5)") (class "Default")
      (node (ref "U5") (pin "5") (pinfunction "RESET_5") (pintype "bidirectional"))
    )
    (net (code "84") (name "unconnected-(U5-SPICLK-Pad6)") (class "Default")
      (node (ref "U5") (pin "6") (pinfunction "SPICLK_6") (pintype "bidirectional"))
    )
    (net (code "85") (name "unconnected-(U5-SPICSB-Pad23)") (class "Default")
      (node (ref "U5") (pin "23") (pinfunction "SPICSB_23") (pintype "bidirectional"))
    )
    (net (code "86") (name "unconnected-(U5-SPIMISO-Pad24)") (class "Default")
      (node (ref "U5") (pin "24") (pinfunction "SPIMISO_24") (pintype "bidirectional"))
    )
    (net (code "87") (name "unconnected-(U5-SPIMOSI-Pad2)") (class "Default")
      (node (ref "U5") (pin "2") (pinfunction "SPIMOSI_2") (pintype "bidirectional"))
    )
    (net (code "88") (name "unconnected-(U5-USBD+-Pad17)") (class "Default")
      (node (ref "U5") (pin "17") (pinfunction "USBD+_17") (pintype "bidirectional"))
    )
    (net (code "89") (name "unconnected-(U5-USBD--Pad18)") (class "Default")
      (node (ref "U5") (pin "18") (pinfunction "USBD-_18") (pintype "bidirectional"))
    )
    (net (code "90") (name "unconnected-(X1-PadD+)") (class "Default")
      (node (ref "X1") (pin "D+") (pinfunction "D+_D+") (pintype "bidirectional"))
    )
    (net (code "91") (name "unconnected-(X1-PadD-)") (class "Default")
      (node (ref "X1") (pin "D-") (pinfunction "D-_D-") (pintype "bidirectional"))
    )
  )
)
